# can_transceiver.net
KiCad netlist of a schematic drawn in Altium Designer
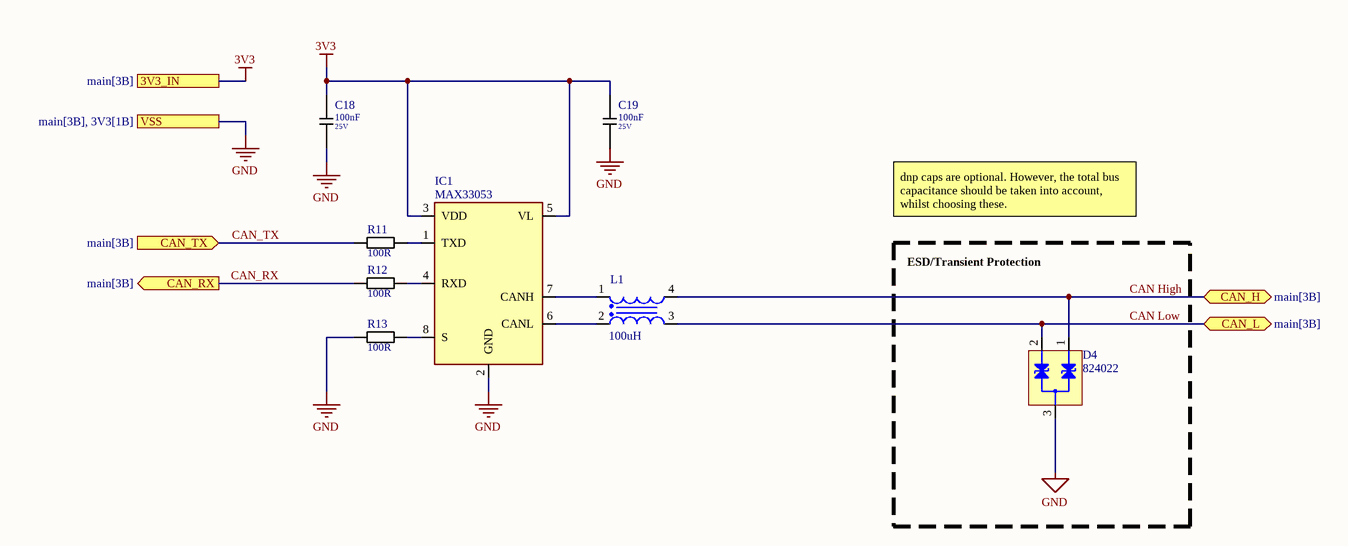
[diagram p0: can_transceiver.SchDoc]

(export (version "E")
  (design (tool "Eeschema 10.0.6"))
  (components
    (comp (ref "C18")
      (value "100nF")
      (footprint "0603_C")
      (description "Keramikkondensatoren 0603")
      (fields (field (name "SPG") "25V") (field (name "Comment") "100nF_25V"))
      (libsource (lib "Allgemeine_ETI_Schematic_Lib") (part "C_0603_Keramik"))
    )
    (comp (ref "C19")
      (value "100nF")
      (footprint "0603_C")
      (description "Keramikkondensatoren 0603")
      (fields (field (name "SPG") "25V") (field (name "Comment") "100nF_25V"))
      (libsource (lib "Allgemeine_ETI_Schematic_Lib") (part "C_0603_Keramik"))
    )
    (comp (ref "D4")
      (value "5V")
      (footprint "WE-TVS_SOT23-3L")
      (description "WE-TVS TVS Diode – Standard Series, SOT23-3L, 2 Channel, 5V, 12pF")
      (fields
        (field (name "MANUFACTURER") "Wurth Elektronik")
        (field (name "MANUFACTURER PART NUMBER") "824022")
      )
      (libsource (lib "KARaceIng25") (part "824022"))
    )
    (comp (ref "IC1")
      (value "MAX33053")
      (footprint "SOIC127P600X175-8N")
      (description "IC TRANSCEIVER FULL 1/1 8SOIC")
      (fields
        (field (name "MOUSER PART NUMBER") "700-MAX33053EASA+T")
        (field (name "MANUFACTURER_PART_NUMBER") "MAX33053EASA+T")
      )
      (libsource (lib "KARaceIng25") (part "MAX33053"))
    )
    (comp (ref "L1")
      (value "100uH")
      (footprint "WE-SLM_L6W3.3H3.3")
      (description "WE-SLM SMT Common Mode Line Filter, 100uH, 0.3A, 0.58Ohm")
      (fields
        (field (name "MANUFACTURER") "Wurth Elektronik")
        (field (name "MANUFACTURER PART NUMBER") "744242101")
        (field (name "INDUCTANCE") "100uH")
      )
      (libsource (lib "KARaceIng25") (part "744242101"))
    )
    (comp (ref "R11")
      (value "100R")
      (footprint "0603_R")
      (description "R 0603, 75V, 0.1W")
      (libsource (lib "Allgemeine_ETI_Schematic_Lib") (part "R_0603"))
    )
    (comp (ref "R12")
      (value "100R")
      (footprint "0603_R")
      (description "R 0603, 75V, 0.1W")
      (libsource (lib "Allgemeine_ETI_Schematic_Lib") (part "R_0603"))
    )
    (comp (ref "R13")
      (value "100R")
      (footprint "0603_R")
      (description "R 0603, 75V, 0.1W")
      (libsource (lib "Allgemeine_ETI_Schematic_Lib") (part "R_0603"))
    )
  )
  (nets
    (net (code "1") (name "/CAN High") (class "Default")
      (node (ref "D4") (pin "1") (pinfunction "I/O_1_1") (pintype "passive"))
      (node (ref "L1") (pin "4") (pinfunction "4_4") (pintype "passive"))
    )
    (net (code "2") (name "/CAN Low") (class "Default")
      (node (ref "D4") (pin "2") (pinfunction "I/O_2_2") (pintype "passive"))
      (node (ref "L1") (pin "3") (pinfunction "3_3") (pintype "passive"))
    )
    (net (code "3") (name "/CAN_RX") (class "Default")
      (node (ref "R12") (pin "1") (pinfunction "1_1") (pintype "passive"))
    )
    (net (code "4") (name "/CAN_TX") (class "Default")
      (node (ref "R11") (pin "1") (pinfunction "1_1") (pintype "passive"))
    )
    (net (code "5") (name "3V3") (class "Default")
      (node (ref "C18") (pin "1") (pinfunction "1_1") (pintype "passive"))
      (node (ref "C19") (pin "1") (pinfunction "1_1") (pintype "passive"))
      (node (ref "IC1") (pin "3") (pinfunction "VDD_3") (pintype "passive"))
      (node (ref "IC1") (pin "5") (pinfunction "VL_5") (pintype "passive"))
    )
    (net (code "6") (name "GND") (class "Default")
      (node (ref "C18") (pin "2") (pinfunction "2_2") (pintype "passive"))
      (node (ref "C19") (pin "2") (pinfunction "2_2") (pintype "passive"))
      (node (ref "D4") (pin "3") (pinfunction "GND_3") (pintype "passive"))
      (node (ref "IC1") (pin "2") (pinfunction "GND_2") (pintype "passive"))
      (node (ref "R13") (pin "1") (pinfunction "1_1") (pintype "passive"))
    )
    (net (code "7") (name "Net-(IC1-CANH)") (class "Default")
      (node (ref "IC1") (pin "7") (pinfunction "CANH_7") (pintype "passive"))
      (node (ref "L1") (pin "1") (pinfunction "1_1") (pintype "passive"))
    )
    (net (code "8") (name "Net-(IC1-CANL)") (class "Default")
      (node (ref "IC1") (pin "6") (pinfunction "CANL_6") (pintype "passive"))
      (node (ref "L1") (pin "2") (pinfunction "2_2") (pintype "passive"))
    )
    (net (code "9") (name "Net-(IC1-RXD)") (class "Default")
      (node (ref "IC1") (pin "4") (pinfunction "RXD_4") (pintype "passive"))
      (node (ref "R12") (pin "2") (pinfunction "2_2") (pintype "passive"))
    )
    (net (code "10") (name "Net-(IC1-S)") (class "Default")
      (node (ref "IC1") (pin "8") (pinfunction "S_8") (pintype "passive"))
      (node (ref "R13") (pin "2") (pinfunction "2_2") (pintype "passive"))
    )
    (net (code "11") (name "Net-(IC1-TXD)") (class "Default")
      (node (ref "IC1") (pin "1") (pinfunction "TXD_1") (pintype "passive"))
      (node (ref "R11") (pin "2") (pinfunction "2_2") (pintype "passive"))
    )
  )
)
